# Thermocouple_Amplifier.net
KiCad netlist of a schematic drawn in Altium Designer
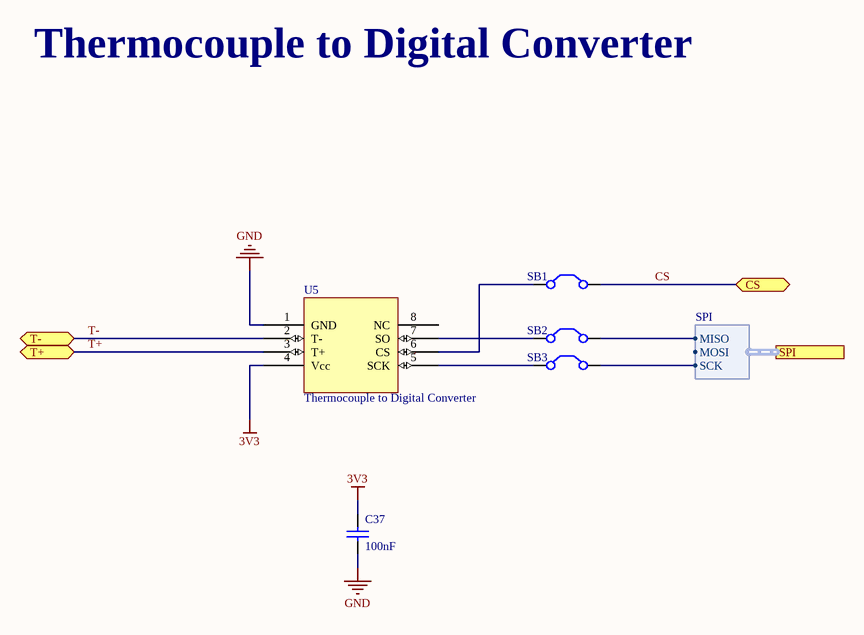
[diagram p0: Thermocouple_Amplifier.SchDoc]

(export (version "E")
  (design (tool "Eeschema 10.0.6"))
  (components
    (comp (ref "C37")
      (value "100nF")
      (footprint "0603")
      (description "Capacitor")
      (fields (field (name "Comment") "Cap"))
      (libsource (lib "Miscellaneous Devices") (part "Cap"))
    )
    (comp (ref "SB1")
      (value "Solder Bridge")
      (footprint "Solder Bridge")
      (description "Jumper Wire")
      (libsource (lib "Miscellaneous Devices") (part "Jumper"))
    )
    (comp (ref "SB2")
      (value "Solder Bridge")
      (footprint "Solder Bridge")
      (description "Jumper Wire")
      (libsource (lib "Miscellaneous Devices") (part "Jumper"))
    )
    (comp (ref "SB3")
      (value "Solder Bridge")
      (footprint "Solder Bridge")
      (description "Jumper Wire")
      (libsource (lib "Miscellaneous Devices") (part "Jumper"))
    )
    (comp (ref "U5")
      (value "Thermocouple to Digital Converter")
      (footprint "8-SOIC MAXIM")
      (libsource (lib "LaunchyRIOComponents") (part "MAX31855x"))
    )
  )
  (nets
    (net (code "2") (name "/CS") (class "Default")
      (node (ref "SB1") (pin "2") (pinfunction "C2_2") (pintype "passive"))
    )
    (net (code "3") (name "/MISO") (class "Default")
      (node (ref "SB2") (pin "2") (pinfunction "C2_2") (pintype "passive"))
    )
    (net (code "4") (name "/SCK") (class "Default")
      (node (ref "SB3") (pin "2") (pinfunction "C2_2") (pintype "passive"))
    )
    (net (code "5") (name "/T+") (class "Default")
      (node (ref "U5") (pin "3") (pinfunction "T+_3") (pintype "bidirectional"))
    )
    (net (code "6") (name "/T-") (class "Default")
      (node (ref "U5") (pin "2") (pinfunction "T-_2") (pintype "bidirectional"))
    )
    (net (code "8") (name "3V3") (class "Default")
      (node (ref "C37") (pin "2") (pinfunction "2_2") (pintype "passive"))
      (node (ref "U5") (pin "4") (pinfunction "Vcc_4") (pintype "power_in"))
    )
    (net (code "9") (name "GND") (class "Default")
      (node (ref "C37") (pin "1") (pinfunction "1_1") (pintype "passive"))
      (node (ref "U5") (pin "1") (pinfunction "GND_1") (pintype "power_in"))
    )
    (net (code "10") (name "Net-(SB1-C1)") (class "Default")
      (node (ref "SB1") (pin "1") (pinfunction "C1_1") (pintype "passive"))
      (node (ref "U5") (pin "6") (pinfunction "CS_6") (pintype "bidirectional"))
    )
    (net (code "11") (name "Net-(SB2-C1)") (class "Default")
      (node (ref "SB2") (pin "1") (pinfunction "C1_1") (pintype "passive"))
      (node (ref "U5") (pin "7") (pinfunction "SO_7") (pintype "bidirectional"))
    )
    (net (code "12") (name "Net-(SB3-C1)") (class "Default")
      (node (ref "SB3") (pin "1") (pinfunction "C1_1") (pintype "passive"))
      (node (ref "U5") (pin "5") (pinfunction "SCK_5") (pintype "bidirectional"))
    )
    (net (code "13") (name "unconnected-(U5-NC-Pad8)") (class "Default")
      (node (ref "U5") (pin "8") (pinfunction "NC_8") (pintype "passive"))
    )
  )
)
